# vape.net
KiCad netlist of a schematic drawn in EAGLE
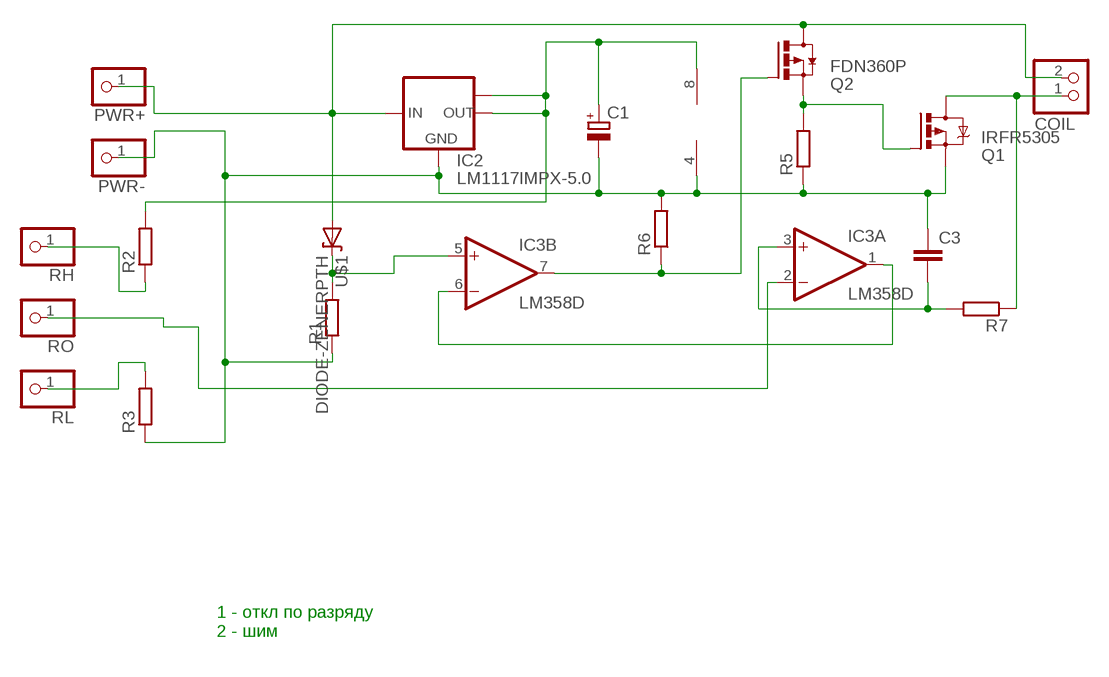
[diagram p0: schematic, sheet 1]

(export (version "E")
  (design (tool "Eeschema 10.0.6"))
  (components
    (comp (ref "C1")
      (value "CPOL-EUSMCD")
      (footprint "eagle-import:SMC_D")
      (libsource (lib "eagle-import") (part "CPOL-EUSMCD"))
    )
    (comp (ref "C3")
      (value "C-EUC1206")
      (footprint "eagle-import:C1206")
      (libsource (lib "eagle-import") (part "C-EUC1206"))
    )
    (comp (ref "COIL")
      (value "PINHD-1X2")
      (footprint "eagle-import:1X02")
      (libsource (lib "eagle-import") (part "PINHD-1X2"))
    )
    (comp (ref "IC2")
      (value "LM1117IMPX-5.0")
      (footprint "eagle-import:SOT223")
      (libsource (lib "eagle-import") (part "LM1117IMPX-5.0"))
    )
    (comp (ref "IC3")
      (value "LM358D")
      (footprint "eagle-import:SO08")
      (libsource (lib "eagle-import") (part "LM358D"))
    )
    (comp (ref "PWR+")
      (value "PINHD-1X1")
      (footprint "eagle-import:1X01")
      (libsource (lib "eagle-import") (part "PINHD-1X1"))
    )
    (comp (ref "PWR-")
      (value "PINHD-1X1")
      (footprint "eagle-import:1X01")
      (libsource (lib "eagle-import") (part "PINHD-1X1"))
    )
    (comp (ref "Q1")
      (value "IRFR5305")
      (footprint "eagle-import:D-PAK_TO252AA")
      (libsource (lib "eagle-import") (part "IRF?5305R"))
    )
    (comp (ref "Q2")
      (value "FDN360P")
      (footprint "eagle-import:SUPER-SOT3")
      (libsource (lib "eagle-import") (part "FDN360P"))
    )
    (comp (ref "R1")
      (value "R-EU_R1206")
      (footprint "eagle-import:R1206")
      (libsource (lib "eagle-import") (part "R-EU_R1206"))
    )
    (comp (ref "R2")
      (value "R-EU_R1206")
      (footprint "eagle-import:R1206")
      (libsource (lib "eagle-import") (part "R-EU_R1206"))
    )
    (comp (ref "R3")
      (value "R-EU_R1206")
      (footprint "eagle-import:R1206")
      (libsource (lib "eagle-import") (part "R-EU_R1206"))
    )
    (comp (ref "R5")
      (value "R-EU_R1206")
      (footprint "eagle-import:R1206")
      (libsource (lib "eagle-import") (part "R-EU_R1206"))
    )
    (comp (ref "R6")
      (value "R-EU_R1206")
      (footprint "eagle-import:R1206")
      (libsource (lib "eagle-import") (part "R-EU_R1206"))
    )
    (comp (ref "R7")
      (value "R-EU_R1206")
      (footprint "eagle-import:R1206")
      (libsource (lib "eagle-import") (part "R-EU_R1206"))
    )
    (comp (ref "RH")
      (value "PINHD-1X1")
      (footprint "eagle-import:1X01")
      (libsource (lib "eagle-import") (part "PINHD-1X1"))
    )
    (comp (ref "RL")
      (value "PINHD-1X1")
      (footprint "eagle-import:1X01")
      (libsource (lib "eagle-import") (part "PINHD-1X1"))
    )
    (comp (ref "RO")
      (value "PINHD-1X1")
      (footprint "eagle-import:1X01")
      (libsource (lib "eagle-import") (part "PINHD-1X1"))
    )
    (comp (ref "U$1")
      (value "DIODE-ZENERPTH")
      (footprint "eagle-import:DIODE-ZENER")
      (libsource (lib "eagle-import") (part "DIODE-ZENERPTH"))
    )
  )
  (nets
    (net (code "1") (name "Net-(IC2-GND)") (class "Default")
      (node (ref "C1") (pin "-") (pinfunction "-_-") (pintype "passive"))
      (node (ref "C3") (pin "1") (pinfunction "1_1") (pintype "passive"))
      (node (ref "IC2") (pin "1") (pinfunction "GND_1") (pintype "input"))
      (node (ref "IC3") (pin "4") (pinfunction "V-_4") (pintype "power_in"))
      (node (ref "PWR-") (pin "1") (pinfunction "1_1") (pintype "passive"))
      (node (ref "Q1") (pin "3") (pinfunction "S_3") (pintype "passive"))
      (node (ref "R1") (pin "1") (pinfunction "1_1") (pintype "passive"))
      (node (ref "R3") (pin "1") (pinfunction "1_1") (pintype "passive"))
      (node (ref "R5") (pin "1") (pinfunction "1_1") (pintype "passive"))
      (node (ref "R6") (pin "2") (pinfunction "2_2") (pintype "passive"))
    )
    (net (code "2") (name "Net-(IC2-IN)") (class "Default")
      (node (ref "COIL") (pin "2") (pinfunction "2_2") (pintype "passive"))
      (node (ref "IC2") (pin "3") (pinfunction "IN_3") (pintype "input"))
      (node (ref "PWR+") (pin "1") (pinfunction "1_1") (pintype "passive"))
      (node (ref "Q2") (pin "3") (pinfunction "D_3") (pintype "passive"))
      (node (ref "U$1") (pin "P$2") (pinfunction "A_P$2") (pintype "passive"))
    )
    (net (code "3") (name "Net-(IC2-OUT)") (class "Default")
      (node (ref "C1") (pin "+") (pinfunction "+_+") (pintype "passive"))
      (node (ref "IC2") (pin "2") (pinfunction "OUT_2") (pintype "passive"))
      (node (ref "IC2") (pin "TAB") (pinfunction "OUT1_TAB") (pintype "passive"))
      (node (ref "IC3") (pin "8") (pinfunction "V+_8") (pintype "power_in"))
      (node (ref "R2") (pin "2") (pinfunction "2_2") (pintype "passive"))
    )
    (net (code "4") (name "Net-(IC3A-+IN)") (class "Default")
      (node (ref "C3") (pin "2") (pinfunction "2_2") (pintype "passive"))
      (node (ref "IC3") (pin "3") (pinfunction "+IN_3") (pintype "input"))
      (node (ref "R7") (pin "2") (pinfunction "2_2") (pintype "passive"))
    )
    (net (code "5") (name "Net-(IC3A--IN)") (class "Default")
      (node (ref "IC3") (pin "2") (pinfunction "-IN_2") (pintype "input"))
      (node (ref "RO") (pin "1") (pinfunction "1_1") (pintype "passive"))
    )
    (net (code "6") (name "Net-(IC3A-OUT)") (class "Default")
      (node (ref "IC3") (pin "1") (pinfunction "OUT_1") (pintype "output"))
      (node (ref "IC3") (pin "6") (pinfunction "-IN_6") (pintype "input"))
    )
    (net (code "7") (name "Net-(IC3B-+IN)") (class "Default")
      (node (ref "IC3") (pin "5") (pinfunction "+IN_5") (pintype "input"))
      (node (ref "R1") (pin "2") (pinfunction "2_2") (pintype "passive"))
      (node (ref "U$1") (pin "P$1") (pinfunction "C_P$1") (pintype "passive"))
    )
    (net (code "8") (name "Net-(IC3B-OUT)") (class "Default")
      (node (ref "IC3") (pin "7") (pinfunction "OUT_7") (pintype "output"))
      (node (ref "Q2") (pin "1") (pinfunction "G_1") (pintype "passive"))
      (node (ref "R6") (pin "1") (pinfunction "1_1") (pintype "passive"))
    )
    (net (code "9") (name "Net-(Q1-D)") (class "Default")
      (node (ref "COIL") (pin "1") (pinfunction "1_1") (pintype "passive"))
      (node (ref "Q1") (pin "4") (pinfunction "D_4") (pintype "passive"))
      (node (ref "R7") (pin "1") (pinfunction "1_1") (pintype "passive"))
    )
    (net (code "10") (name "Net-(Q1-G)") (class "Default")
      (node (ref "Q1") (pin "1") (pinfunction "G_1") (pintype "passive"))
      (node (ref "Q2") (pin "2") (pinfunction "S_2") (pintype "passive"))
      (node (ref "R5") (pin "2") (pinfunction "2_2") (pintype "passive"))
    )
    (net (code "11") (name "Net-(R2-Pad1)") (class "Default")
      (node (ref "R2") (pin "1") (pinfunction "1_1") (pintype "passive"))
      (node (ref "RH") (pin "1") (pinfunction "1_1") (pintype "passive"))
    )
    (net (code "12") (name "Net-(R3-Pad2)") (class "Default")
      (node (ref "R3") (pin "2") (pinfunction "2_2") (pintype "passive"))
      (node (ref "RL") (pin "1") (pinfunction "1_1") (pintype "passive"))
    )
  )
)
